# PCA_0006_Mini_CB_80Pin_REV_B.net
KiCad netlist of a schematic drawn in Altium Designer
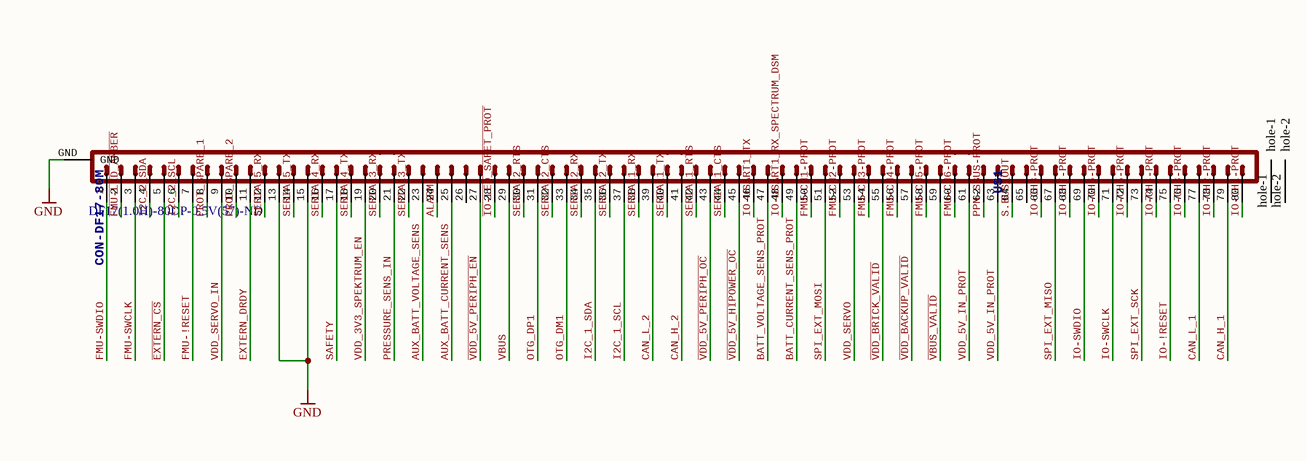
[diagram p0: PCA_0006_Mini_CB_80Pin_REV_B.SchDoc]

(export (version "E")
  (design (tool "Eeschema 10.0.6"))
  (components
    (comp (ref "U$1")
      (value "CON-DF17-80M")
      (footprint "CON-DF17-80M")
      (description "Connector, Header, 80Pos, .5MM, DUAL, SMD, Au")
      (fields
        (field (name "SUPPLIER PART NUMBER 1") "DF17(1.0H)-80DP-0.5V(57)-ND")
        (field (name "3DR_PARTNO") "ECM0528")
      )
      (libsource (lib "PCA_0006_Mini_CB_REV_A") (part "CON-DF17-80M"))
    )
  )
  (nets
    (net (code "1") (name "/ALARM") (class "Default")
      (node (ref "U$1") (pin "24") (pinfunction "24_24") (pintype "passive"))
    )
    (net (code "2") (name "/AUX_BATT_CURRENT_SENS") (class "Default")
      (node (ref "U$1") (pin "25") (pinfunction "25_25") (pintype "passive"))
    )
    (net (code "3") (name "/AUX_BATT_VOLTAGE_SENS") (class "Default")
      (node (ref "U$1") (pin "23") (pinfunction "23_23") (pintype "passive"))
    )
    (net (code "4") (name "/BATT_CURRENT_SENS_PROT") (class "Default")
      (node (ref "U$1") (pin "49") (pinfunction "49_49") (pintype "passive"))
    )
    (net (code "5") (name "/BATT_VOLTAGE_SENS_PROT") (class "Default")
      (node (ref "U$1") (pin "47") (pinfunction "47_47") (pintype "passive"))
    )
    (net (code "6") (name "/CAN_H_1") (class "Default")
      (node (ref "U$1") (pin "79") (pinfunction "79_79") (pintype "passive"))
    )
    (net (code "7") (name "/CAN_H_2") (class "Default")
      (node (ref "U$1") (pin "41") (pinfunction "41_41") (pintype "passive"))
    )
    (net (code "8") (name "/CAN_L_1") (class "Default")
      (node (ref "U$1") (pin "77") (pinfunction "77_77") (pintype "passive"))
    )
    (net (code "9") (name "/CAN_L_2") (class "Default")
      (node (ref "U$1") (pin "39") (pinfunction "39_39") (pintype "passive"))
    )
    (net (code "10") (name "/EXTERN_DRDY") (class "Default")
      (node (ref "U$1") (pin "11") (pinfunction "11_11") (pintype "passive"))
    )
    (net (code "11") (name "/FMU-!RESET") (class "Default")
      (node (ref "U$1") (pin "7") (pinfunction "7_7") (pintype "passive"))
    )
    (net (code "12") (name "/FMU-CH1-PROT") (class "Default")
      (node (ref "U$1") (pin "50") (pinfunction "50_50") (pintype "passive"))
    )
    (net (code "13") (name "/FMU-CH2-PROT") (class "Default")
      (node (ref "U$1") (pin "52") (pinfunction "52_52") (pintype "passive"))
    )
    (net (code "14") (name "/FMU-CH3-PROT") (class "Default")
      (node (ref "U$1") (pin "54") (pinfunction "54_54") (pintype "passive"))
    )
    (net (code "15") (name "/FMU-CH4-PROT") (class "Default")
      (node (ref "U$1") (pin "56") (pinfunction "56_56") (pintype "passive"))
    )
    (net (code "16") (name "/FMU-CH5-PROT") (class "Default")
      (node (ref "U$1") (pin "58") (pinfunction "58_58") (pintype "passive"))
    )
    (net (code "17") (name "/FMU-CH6-PROT") (class "Default")
      (node (ref "U$1") (pin "60") (pinfunction "60_60") (pintype "passive"))
    )
    (net (code "18") (name "/FMU-SWCLK") (class "Default")
      (node (ref "U$1") (pin "3") (pinfunction "3_3") (pintype "passive"))
    )
    (net (code "19") (name "/FMU-SWDIO") (class "Default")
      (node (ref "U$1") (pin "1") (pinfunction "1_1") (pintype "passive"))
    )
    (net (code "20") (name "/I2C_1_SCL") (class "Default")
      (node (ref "U$1") (pin "37") (pinfunction "37_37") (pintype "passive"))
    )
    (net (code "21") (name "/I2C_1_SDA") (class "Default")
      (node (ref "U$1") (pin "35") (pinfunction "35_35") (pintype "passive"))
    )
    (net (code "22") (name "/I2C_2_SCL") (class "Default")
      (node (ref "U$1") (pin "6") (pinfunction "6_6") (pintype "passive"))
    )
    (net (code "23") (name "/I2C_2_SDA") (class "Default")
      (node (ref "U$1") (pin "4") (pinfunction "4_4") (pintype "passive"))
    )
    (net (code "24") (name "/IO-!RESET") (class "Default")
      (node (ref "U$1") (pin "75") (pinfunction "75_75") (pintype "passive"))
    )
    (net (code "25") (name "/IO-CH1-PROT") (class "Default")
      (node (ref "U$1") (pin "80") (pinfunction "80_80") (pintype "passive"))
    )
    (net (code "26") (name "/IO-CH2-PROT") (class "Default")
      (node (ref "U$1") (pin "78") (pinfunction "78_78") (pintype "passive"))
    )
    (net (code "27") (name "/IO-CH3-PROT") (class "Default")
      (node (ref "U$1") (pin "76") (pinfunction "76_76") (pintype "passive"))
    )
    (net (code "28") (name "/IO-CH4-PROT") (class "Default")
      (node (ref "U$1") (pin "74") (pinfunction "74_74") (pintype "passive"))
    )
    (net (code "29") (name "/IO-CH5-PROT") (class "Default")
      (node (ref "U$1") (pin "72") (pinfunction "72_72") (pintype "passive"))
    )
    (net (code "30") (name "/IO-CH6-PROT") (class "Default")
      (node (ref "U$1") (pin "70") (pinfunction "70_70") (pintype "passive"))
    )
    (net (code "31") (name "/IO-CH7-PROT") (class "Default")
      (node (ref "U$1") (pin "68") (pinfunction "68_68") (pintype "passive"))
    )
    (net (code "32") (name "/IO-CH8-PROT") (class "Default")
      (node (ref "U$1") (pin "66") (pinfunction "66_66") (pintype "passive"))
    )
    (net (code "33") (name "/IO-SWCLK") (class "Default")
      (node (ref "U$1") (pin "71") (pinfunction "71_71") (pintype "passive"))
    )
    (net (code "34") (name "/IO-SWDIO") (class "Default")
      (node (ref "U$1") (pin "69") (pinfunction "69_69") (pintype "passive"))
    )
    (net (code "35") (name "/IO-USART1_RX_SPECTRUM_DSM") (class "Default")
      (node (ref "U$1") (pin "48") (pinfunction "48_48") (pintype "passive"))
    )
    (net (code "36") (name "/IO-USART1_TX") (class "Default")
      (node (ref "U$1") (pin "46") (pinfunction "46_46") (pintype "passive"))
    )
    (net (code "37") (name "/OTG_DM1") (class "Default")
      (node (ref "U$1") (pin "33") (pinfunction "33_33") (pintype "passive"))
    )
    (net (code "38") (name "/OTG_DP1") (class "Default")
      (node (ref "U$1") (pin "31") (pinfunction "31_31") (pintype "passive"))
    )
    (net (code "39") (name "/PPM-SBUS-PROT") (class "Default")
      (node (ref "U$1") (pin "62") (pinfunction "62_62") (pintype "passive"))
    )
    (net (code "40") (name "/PRESSURE_SENS_IN") (class "Default")
      (node (ref "U$1") (pin "21") (pinfunction "21_21") (pintype "passive"))
    )
    (net (code "41") (name "/PROT_SPARE_1") (class "Default")
      (node (ref "U$1") (pin "8") (pinfunction "8_8") (pintype "passive"))
    )
    (net (code "42") (name "/PROT_SPARE_2") (class "Default")
      (node (ref "U$1") (pin "10") (pinfunction "10_10") (pintype "passive"))
    )
    (net (code "43") (name "/S.BUS_OUT") (class "Default")
      (node (ref "U$1") (pin "64") (pinfunction "64_64") (pintype "passive"))
    )
    (net (code "44") (name "/SAFETY") (class "Default")
      (node (ref "U$1") (pin "17") (pinfunction "17_17") (pintype "passive"))
    )
    (net (code "45") (name "/SERIAL1_CTS") (class "Default")
      (node (ref "U$1") (pin "44") (pinfunction "44_44") (pintype "passive"))
    )
    (net (code "46") (name "/SERIAL1_RTS") (class "Default")
      (node (ref "U$1") (pin "42") (pinfunction "42_42") (pintype "passive"))
    )
    (net (code "47") (name "/SERIAL1_RX") (class "Default")
      (node (ref "U$1") (pin "38") (pinfunction "38_38") (pintype "passive"))
    )
    (net (code "48") (name "/SERIAL1_TX") (class "Default")
      (node (ref "U$1") (pin "40") (pinfunction "40_40") (pintype "passive"))
    )
    (net (code "49") (name "/SERIAL2_CTS") (class "Default")
      (node (ref "U$1") (pin "32") (pinfunction "32_32") (pintype "passive"))
    )
    (net (code "50") (name "/SERIAL2_RTS") (class "Default")
      (node (ref "U$1") (pin "30") (pinfunction "30_30") (pintype "passive"))
    )
    (net (code "51") (name "/SERIAL2_RX") (class "Default")
      (node (ref "U$1") (pin "34") (pinfunction "34_34") (pintype "passive"))
    )
    (net (code "52") (name "/SERIAL2_TX") (class "Default")
      (node (ref "U$1") (pin "36") (pinfunction "36_36") (pintype "passive"))
    )
    (net (code "53") (name "/SERIAL3_RX") (class "Default")
      (node (ref "U$1") (pin "20") (pinfunction "20_20") (pintype "passive"))
    )
    (net (code "54") (name "/SERIAL3_TX") (class "Default")
      (node (ref "U$1") (pin "22") (pinfunction "22_22") (pintype "passive"))
    )
    (net (code "55") (name "/SERIAL4_RX") (class "Default")
      (node (ref "U$1") (pin "16") (pinfunction "16_16") (pintype "passive"))
    )
    (net (code "56") (name "/SERIAL4_TX") (class "Default")
      (node (ref "U$1") (pin "18") (pinfunction "18_18") (pintype "passive"))
    )
    (net (code "57") (name "/SERIAL5_RX") (class "Default")
      (node (ref "U$1") (pin "12") (pinfunction "12_12") (pintype "passive"))
    )
    (net (code "58") (name "/SERIAL5_TX") (class "Default")
      (node (ref "U$1") (pin "14") (pinfunction "14_14") (pintype "passive"))
    )
    (net (code "59") (name "/SPI_EXT_MISO") (class "Default")
      (node (ref "U$1") (pin "67") (pinfunction "67_67") (pintype "passive"))
    )
    (net (code "60") (name "/SPI_EXT_MOSI") (class "Default")
      (node (ref "U$1") (pin "51") (pinfunction "51_51") (pintype "passive"))
    )
    (net (code "61") (name "/SPI_EXT_SCK") (class "Default")
      (node (ref "U$1") (pin "73") (pinfunction "73_73") (pintype "passive"))
    )
    (net (code "62") (name "/VBUS") (class "Default")
      (node (ref "U$1") (pin "29") (pinfunction "29_29") (pintype "passive"))
    )
    (net (code "63") (name "/VDD_3V3_SPEKTRUM_EN") (class "Default")
      (node (ref "U$1") (pin "19") (pinfunction "19_19") (pintype "passive"))
    )
    (net (code "64") (name "/VDD_5V_IN_PROT") (class "Default")
      (node (ref "U$1") (pin "61") (pinfunction "61_61") (pintype "passive"))
      (node (ref "U$1") (pin "63") (pinfunction "63_63") (pintype "passive"))
    )
    (net (code "65") (name "/VDD_SERVO") (class "Default")
      (node (ref "U$1") (pin "53") (pinfunction "53_53") (pintype "passive"))
    )
    (net (code "66") (name "/VDD_SERVO_IN") (class "Default")
      (node (ref "U$1") (pin "9") (pinfunction "9_9") (pintype "passive"))
    )
    (net (code "67") (name "/~{EXTERN_CS}") (class "Default")
      (node (ref "U$1") (pin "5") (pinfunction "5_5") (pintype "passive"))
    )
    (net (code "68") (name "/~{FMU-LED_AMBER}") (class "Default")
      (node (ref "U$1") (pin "2") (pinfunction "2_2") (pintype "passive"))
    )
    (net (code "69") (name "/~{IO-LED_SAFET_PROT}") (class "Default")
      (node (ref "U$1") (pin "28") (pinfunction "28_28") (pintype "passive"))
    )
    (net (code "70") (name "/~{VBUS_VALID}") (class "Default")
      (node (ref "U$1") (pin "59") (pinfunction "59_59") (pintype "passive"))
    )
    (net (code "71") (name "/~{VDD_5V_HIPOWER_OC}") (class "Default")
      (node (ref "U$1") (pin "45") (pinfunction "45_45") (pintype "passive"))
    )
    (net (code "72") (name "/~{VDD_5V_PERIPH_EN}") (class "Default")
      (node (ref "U$1") (pin "27") (pinfunction "27_27") (pintype "passive"))
    )
    (net (code "73") (name "/~{VDD_5V_PERIPH_OC}") (class "Default")
      (node (ref "U$1") (pin "43") (pinfunction "43_43") (pintype "passive"))
    )
    (net (code "74") (name "/~{VDD_BACKUP_VALID}") (class "Default")
      (node (ref "U$1") (pin "57") (pinfunction "57_57") (pintype "passive"))
    )
    (net (code "75") (name "/~{VDD_BRICK_VALID}") (class "Default")
      (node (ref "U$1") (pin "55") (pinfunction "55_55") (pintype "passive"))
    )
    (net (code "76") (name "GND") (class "Default")
      (node (ref "U$1") (pin "13") (pinfunction "13_13") (pintype "passive"))
      (node (ref "U$1") (pin "15") (pinfunction "15_15") (pintype "passive"))
      (node (ref "U$1") (pin "GND") (pinfunction "GND_GND") (pintype "passive"))
    )
    (net (code "77") (name "unconnected-(U$1-Pad26)") (class "Default")
      (node (ref "U$1") (pin "26") (pinfunction "26_26") (pintype "passive"))
    )
    (net (code "78") (name "unconnected-(U$1-Pad65)") (class "Default")
      (node (ref "U$1") (pin "65") (pinfunction "65_65") (pintype "passive"))
    )
    (net (code "79") (name "unconnected-(U$1-Padhole-1)") (class "Default")
      (node (ref "U$1") (pin "hole-1") (pinfunction "hole-1_hole-1") (pintype "passive"))
    )
    (net (code "80") (name "unconnected-(U$1-Padhole-2)") (class "Default")
      (node (ref "U$1") (pin "hole-2") (pinfunction "hole-2_hole-2") (pintype "passive"))
    )
  )
)
